# Sheet1.net
KiCad netlist of a schematic drawn in Altium Designer
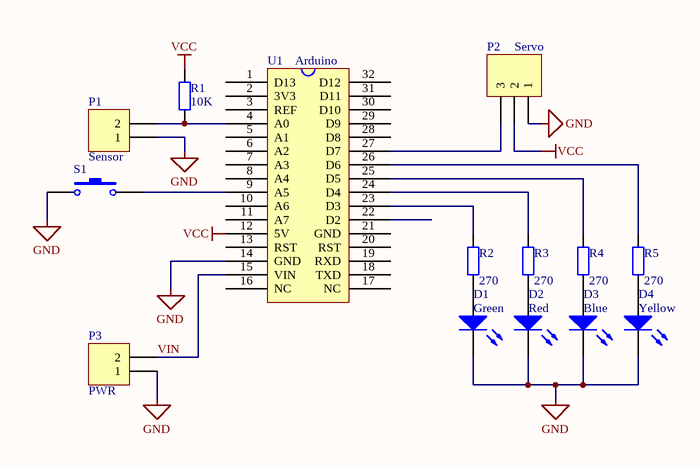
[diagram p0: Sheet1.SchDoc]

(export (version "E")
  (design (tool "Eeschema 10.0.6"))
  (components
    (comp (ref "D1")
      (value "Green")
      (footprint "LED_3mm")
      (description "Typical INFRARED GaAs LED")
      (fields (field (name "PUBLISHER") "Altium Limited"))
      (libsource (lib "Miscellaneous Devices") (part "LED0"))
    )
    (comp (ref "D2")
      (value "Red")
      (footprint "LED_3mm")
      (description "Typical INFRARED GaAs LED")
      (fields (field (name "PUBLISHER") "Altium Limited"))
      (libsource (lib "Miscellaneous Devices") (part "LED0"))
    )
    (comp (ref "D3")
      (value "Blue")
      (footprint "LED_3mm")
      (description "Typical INFRARED GaAs LED")
      (fields (field (name "PUBLISHER") "Altium Limited"))
      (libsource (lib "Miscellaneous Devices") (part "LED0"))
    )
    (comp (ref "D4")
      (value "Yellow")
      (footprint "LED_3mm")
      (description "Typical INFRARED GaAs LED")
      (fields (field (name "PUBLISHER") "Altium Limited"))
      (libsource (lib "Miscellaneous Devices") (part "LED0"))
    )
    (comp (ref "P1")
      (value "Sensor")
      (footprint "HDR1X2")
      (description "Header, 2-Pin")
      (fields (field (name "PUBLISHER") "Altium Limited"))
      (libsource (lib "Miscellaneous Connectors") (part "Header 2"))
    )
    (comp (ref "P2")
      (value "Servo")
      (footprint "HDR1X3")
      (description "Header, 3-Pin")
      (fields (field (name "PUBLISHER") "Altium Limited"))
      (libsource (lib "Miscellaneous Connectors") (part "Header 3"))
    )
    (comp (ref "P3")
      (value "PWR")
      (footprint "HDR1X2")
      (description "Header, 2-Pin")
      (fields (field (name "PUBLISHER") "Altium Limited"))
      (libsource (lib "Miscellaneous Connectors") (part "Header 2"))
    )
    (comp (ref "R1")
      (value "10K")
      (footprint "AXIAL-0.3")
      (description "Resistor")
      (fields (field (name "Comment") "Res2") (field (name "PUBLISHER") "Altium Limited"))
      (libsource (lib "Miscellaneous Devices") (part "Res2"))
    )
    (comp (ref "R2")
      (value "270")
      (footprint "AXIAL-0.3")
      (description "Resistor")
      (fields (field (name "Comment") "Res2") (field (name "PUBLISHER") "Altium Limited"))
      (libsource (lib "Miscellaneous Devices") (part "Res2"))
    )
    (comp (ref "R3")
      (value "270")
      (footprint "AXIAL-0.3")
      (description "Resistor")
      (fields (field (name "Comment") "Res2") (field (name "PUBLISHER") "Altium Limited"))
      (libsource (lib "Miscellaneous Devices") (part "Res2"))
    )
    (comp (ref "R4")
      (value "270")
      (footprint "AXIAL-0.3")
      (description "Resistor")
      (fields (field (name "Comment") "Res2") (field (name "PUBLISHER") "Altium Limited"))
      (libsource (lib "Miscellaneous Devices") (part "Res2"))
    )
    (comp (ref "R5")
      (value "270")
      (footprint "AXIAL-0.3")
      (description "Resistor")
      (fields (field (name "Comment") "Res2") (field (name "PUBLISHER") "Altium Limited"))
      (libsource (lib "Miscellaneous Devices") (part "Res2"))
    )
    (comp (ref "S1")
      (value "SW-PB")
      (footprint "SW")
      (description "Switch")
      (fields (field (name "PUBLISHER") "Altium Limited"))
      (libsource (lib "Miscellaneous Devices") (part "SW-PB"))
    )
    (comp (ref "U1")
      (value "Arduino")
      (footprint "Arduino_nano")
      (libsource (lib "mylib") (part "Arduino_nano"))
    )
  )
  (nets
    (net (code "1") (name "/VIN") (class "Default")
      (node (ref "P3") (pin "2") (pinfunction "2_2") (pintype "passive"))
      (node (ref "U1") (pin "15") (pinfunction "VIN_15") (pintype "passive"))
    )
    (net (code "2") (name "GND") (class "Default")
      (node (ref "D1") (pin "2") (pinfunction "K_2") (pintype "passive"))
      (node (ref "D2") (pin "2") (pinfunction "K_2") (pintype "passive"))
      (node (ref "D3") (pin "2") (pinfunction "K_2") (pintype "passive"))
      (node (ref "D4") (pin "2") (pinfunction "K_2") (pintype "passive"))
      (node (ref "P1") (pin "1") (pinfunction "1_1") (pintype "passive"))
      (node (ref "P2") (pin "1") (pinfunction "1_1") (pintype "passive"))
      (node (ref "P3") (pin "1") (pinfunction "1_1") (pintype "passive"))
      (node (ref "S1") (pin "1") (pinfunction "1_1") (pintype "passive"))
      (node (ref "U1") (pin "14") (pinfunction "GND_14") (pintype "passive"))
    )
    (net (code "3") (name "Net-(D1-A)") (class "Default")
      (node (ref "D1") (pin "1") (pinfunction "A_1") (pintype "passive"))
      (node (ref "R2") (pin "1") (pinfunction "1_1") (pintype "passive"))
    )
    (net (code "4") (name "Net-(D2-A)") (class "Default")
      (node (ref "D2") (pin "1") (pinfunction "A_1") (pintype "passive"))
      (node (ref "R3") (pin "1") (pinfunction "1_1") (pintype "passive"))
    )
    (net (code "5") (name "Net-(D3-A)") (class "Default")
      (node (ref "D3") (pin "1") (pinfunction "A_1") (pintype "passive"))
      (node (ref "R4") (pin "1") (pinfunction "1_1") (pintype "passive"))
    )
    (net (code "6") (name "Net-(D4-A)") (class "Default")
      (node (ref "D4") (pin "1") (pinfunction "A_1") (pintype "passive"))
      (node (ref "R5") (pin "1") (pinfunction "1_1") (pintype "passive"))
    )
    (net (code "7") (name "Net-(U1-A0)") (class "Default")
      (node (ref "P1") (pin "2") (pinfunction "2_2") (pintype "passive"))
      (node (ref "R1") (pin "1") (pinfunction "1_1") (pintype "passive"))
      (node (ref "U1") (pin "4") (pinfunction "A0_4") (pintype "passive"))
    )
    (net (code "8") (name "Net-(U1-A5)") (class "Default")
      (node (ref "S1") (pin "2") (pinfunction "2_2") (pintype "passive"))
      (node (ref "U1") (pin "9") (pinfunction "A5_9") (pintype "passive"))
    )
    (net (code "9") (name "Net-(U1-D3)") (class "Default")
      (node (ref "R2") (pin "2") (pinfunction "2_2") (pintype "passive"))
      (node (ref "U1") (pin "23") (pinfunction "D3_23") (pintype "passive"))
    )
    (net (code "10") (name "Net-(U1-D4)") (class "Default")
      (node (ref "R3") (pin "2") (pinfunction "2_2") (pintype "passive"))
      (node (ref "U1") (pin "24") (pinfunction "D4_24") (pintype "passive"))
    )
    (net (code "11") (name "Net-(U1-D5)") (class "Default")
      (node (ref "R4") (pin "2") (pinfunction "2_2") (pintype "passive"))
      (node (ref "U1") (pin "25") (pinfunction "D5_25") (pintype "passive"))
    )
    (net (code "12") (name "Net-(U1-D6)") (class "Default")
      (node (ref "R5") (pin "2") (pinfunction "2_2") (pintype "passive"))
      (node (ref "U1") (pin "26") (pinfunction "D6_26") (pintype "passive"))
    )
    (net (code "13") (name "Net-(U1-D7)") (class "Default")
      (node (ref "P2") (pin "3") (pinfunction "3_3") (pintype "passive"))
      (node (ref "U1") (pin "27") (pinfunction "D7_27") (pintype "passive"))
    )
    (net (code "14") (name "VCC") (class "Default")
      (node (ref "P2") (pin "2") (pinfunction "2_2") (pintype "passive"))
      (node (ref "R1") (pin "2") (pinfunction "2_2") (pintype "passive"))
      (node (ref "U1") (pin "12") (pinfunction "5V_12") (pintype "passive"))
    )
    (net (code "15") (name "unconnected-(U1-3V3-Pad2)") (class "Default")
      (node (ref "U1") (pin "2") (pinfunction "3V3_2") (pintype "passive"))
    )
    (net (code "16") (name "unconnected-(U1-A1-Pad5)") (class "Default")
      (node (ref "U1") (pin "5") (pinfunction "A1_5") (pintype "passive"))
    )
    (net (code "17") (name "unconnected-(U1-A2-Pad6)") (class "Default")
      (node (ref "U1") (pin "6") (pinfunction "A2_6") (pintype "passive"))
    )
    (net (code "18") (name "unconnected-(U1-A3-Pad7)") (class "Default")
      (node (ref "U1") (pin "7") (pinfunction "A3_7") (pintype "passive"))
    )
    (net (code "19") (name "unconnected-(U1-A4-Pad8)") (class "Default")
      (node (ref "U1") (pin "8") (pinfunction "A4_8") (pintype "passive"))
    )
    (net (code "20") (name "unconnected-(U1-A6-Pad10)") (class "Default")
      (node (ref "U1") (pin "10") (pinfunction "A6_10") (pintype "passive"))
    )
    (net (code "21") (name "unconnected-(U1-A7-Pad11)") (class "Default")
      (node (ref "U1") (pin "11") (pinfunction "A7_11") (pintype "passive"))
    )
    (net (code "22") (name "unconnected-(U1-D2-Pad22)") (class "Default")
      (node (ref "U1") (pin "22") (pinfunction "D2_22") (pintype "passive"))
    )
    (net (code "23") (name "unconnected-(U1-D8-Pad28)") (class "Default")
      (node (ref "U1") (pin "28") (pinfunction "D8_28") (pintype "passive"))
    )
    (net (code "24") (name "unconnected-(U1-D9-Pad29)") (class "Default")
      (node (ref "U1") (pin "29") (pinfunction "D9_29") (pintype "passive"))
    )
    (net (code "25") (name "unconnected-(U1-D10-Pad30)") (class "Default")
      (node (ref "U1") (pin "30") (pinfunction "D10_30") (pintype "passive"))
    )
    (net (code "26") (name "unconnected-(U1-D11-Pad31)") (class "Default")
      (node (ref "U1") (pin "31") (pinfunction "D11_31") (pintype "passive"))
    )
    (net (code "27") (name "unconnected-(U1-D12-Pad32)") (class "Default")
      (node (ref "U1") (pin "32") (pinfunction "D12_32") (pintype "passive"))
    )
    (net (code "28") (name "unconnected-(U1-D13-Pad1)") (class "Default")
      (node (ref "U1") (pin "1") (pinfunction "D13_1") (pintype "passive"))
    )
    (net (code "29") (name "unconnected-(U1-GND-Pad21)") (class "Default")
      (node (ref "U1") (pin "21") (pinfunction "GND_21") (pintype "passive"))
    )
    (net (code "30") (name "unconnected-(U1-NC-Pad16)") (class "Default")
      (node (ref "U1") (pin "16") (pinfunction "NC_16") (pintype "passive"))
    )
    (net (code "31") (name "unconnected-(U1-NC-Pad17)") (class "Default")
      (node (ref "U1") (pin "17") (pinfunction "NC_17") (pintype "passive"))
    )
    (net (code "32") (name "unconnected-(U1-REF-Pad3)") (class "Default")
      (node (ref "U1") (pin "3") (pinfunction "REF_3") (pintype "passive"))
    )
    (net (code "33") (name "unconnected-(U1-RST-Pad13)") (class "Default")
      (node (ref "U1") (pin "13") (pinfunction "RST_13") (pintype "passive"))
    )
    (net (code "34") (name "unconnected-(U1-RST-Pad20)") (class "Default")
      (node (ref "U1") (pin "20") (pinfunction "RST_20") (pintype "passive"))
    )
    (net (code "35") (name "unconnected-(U1-RXD-Pad19)") (class "Default")
      (node (ref "U1") (pin "19") (pinfunction "RXD_19") (pintype "passive"))
    )
    (net (code "36") (name "unconnected-(U1-TXD-Pad18)") (class "Default")
      (node (ref "U1") (pin "18") (pinfunction "TXD_18") (pintype "passive"))
    )
  )
)
